# num_one.net
KiCad netlist of a schematic drawn in Altium Designer
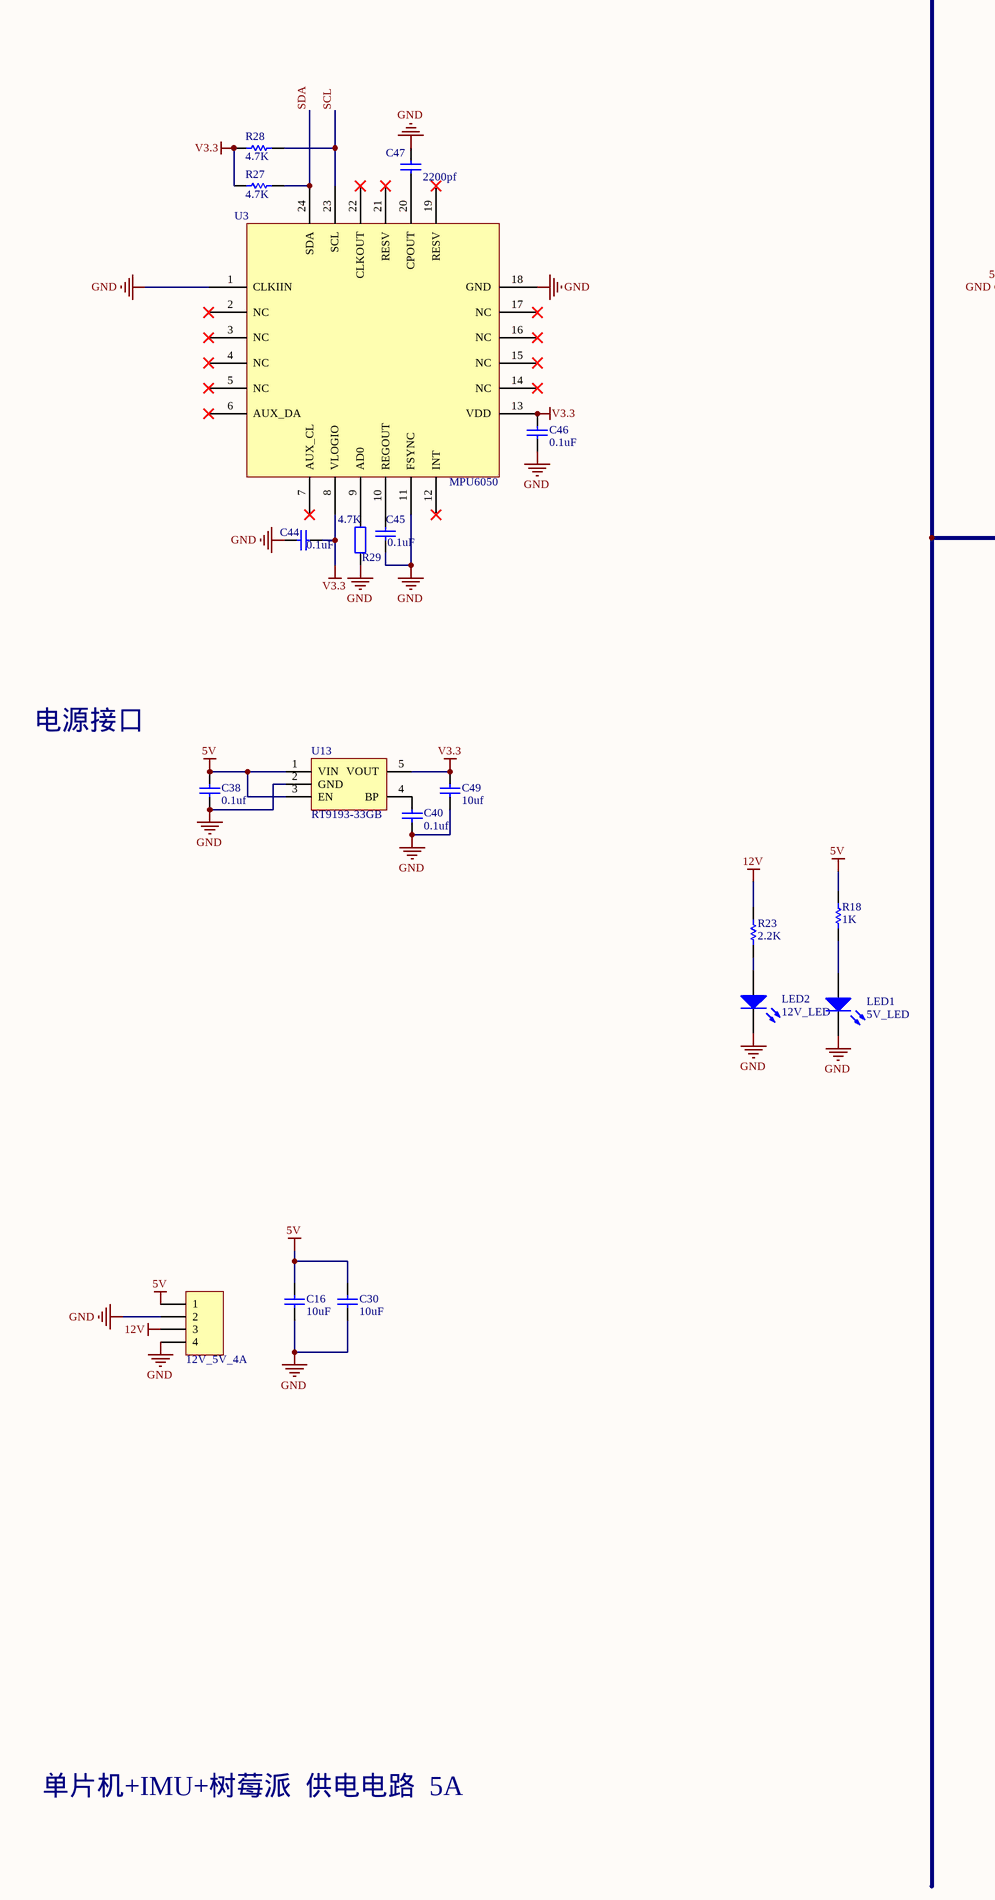
[diagram p0: num_one.SchDoc, left]
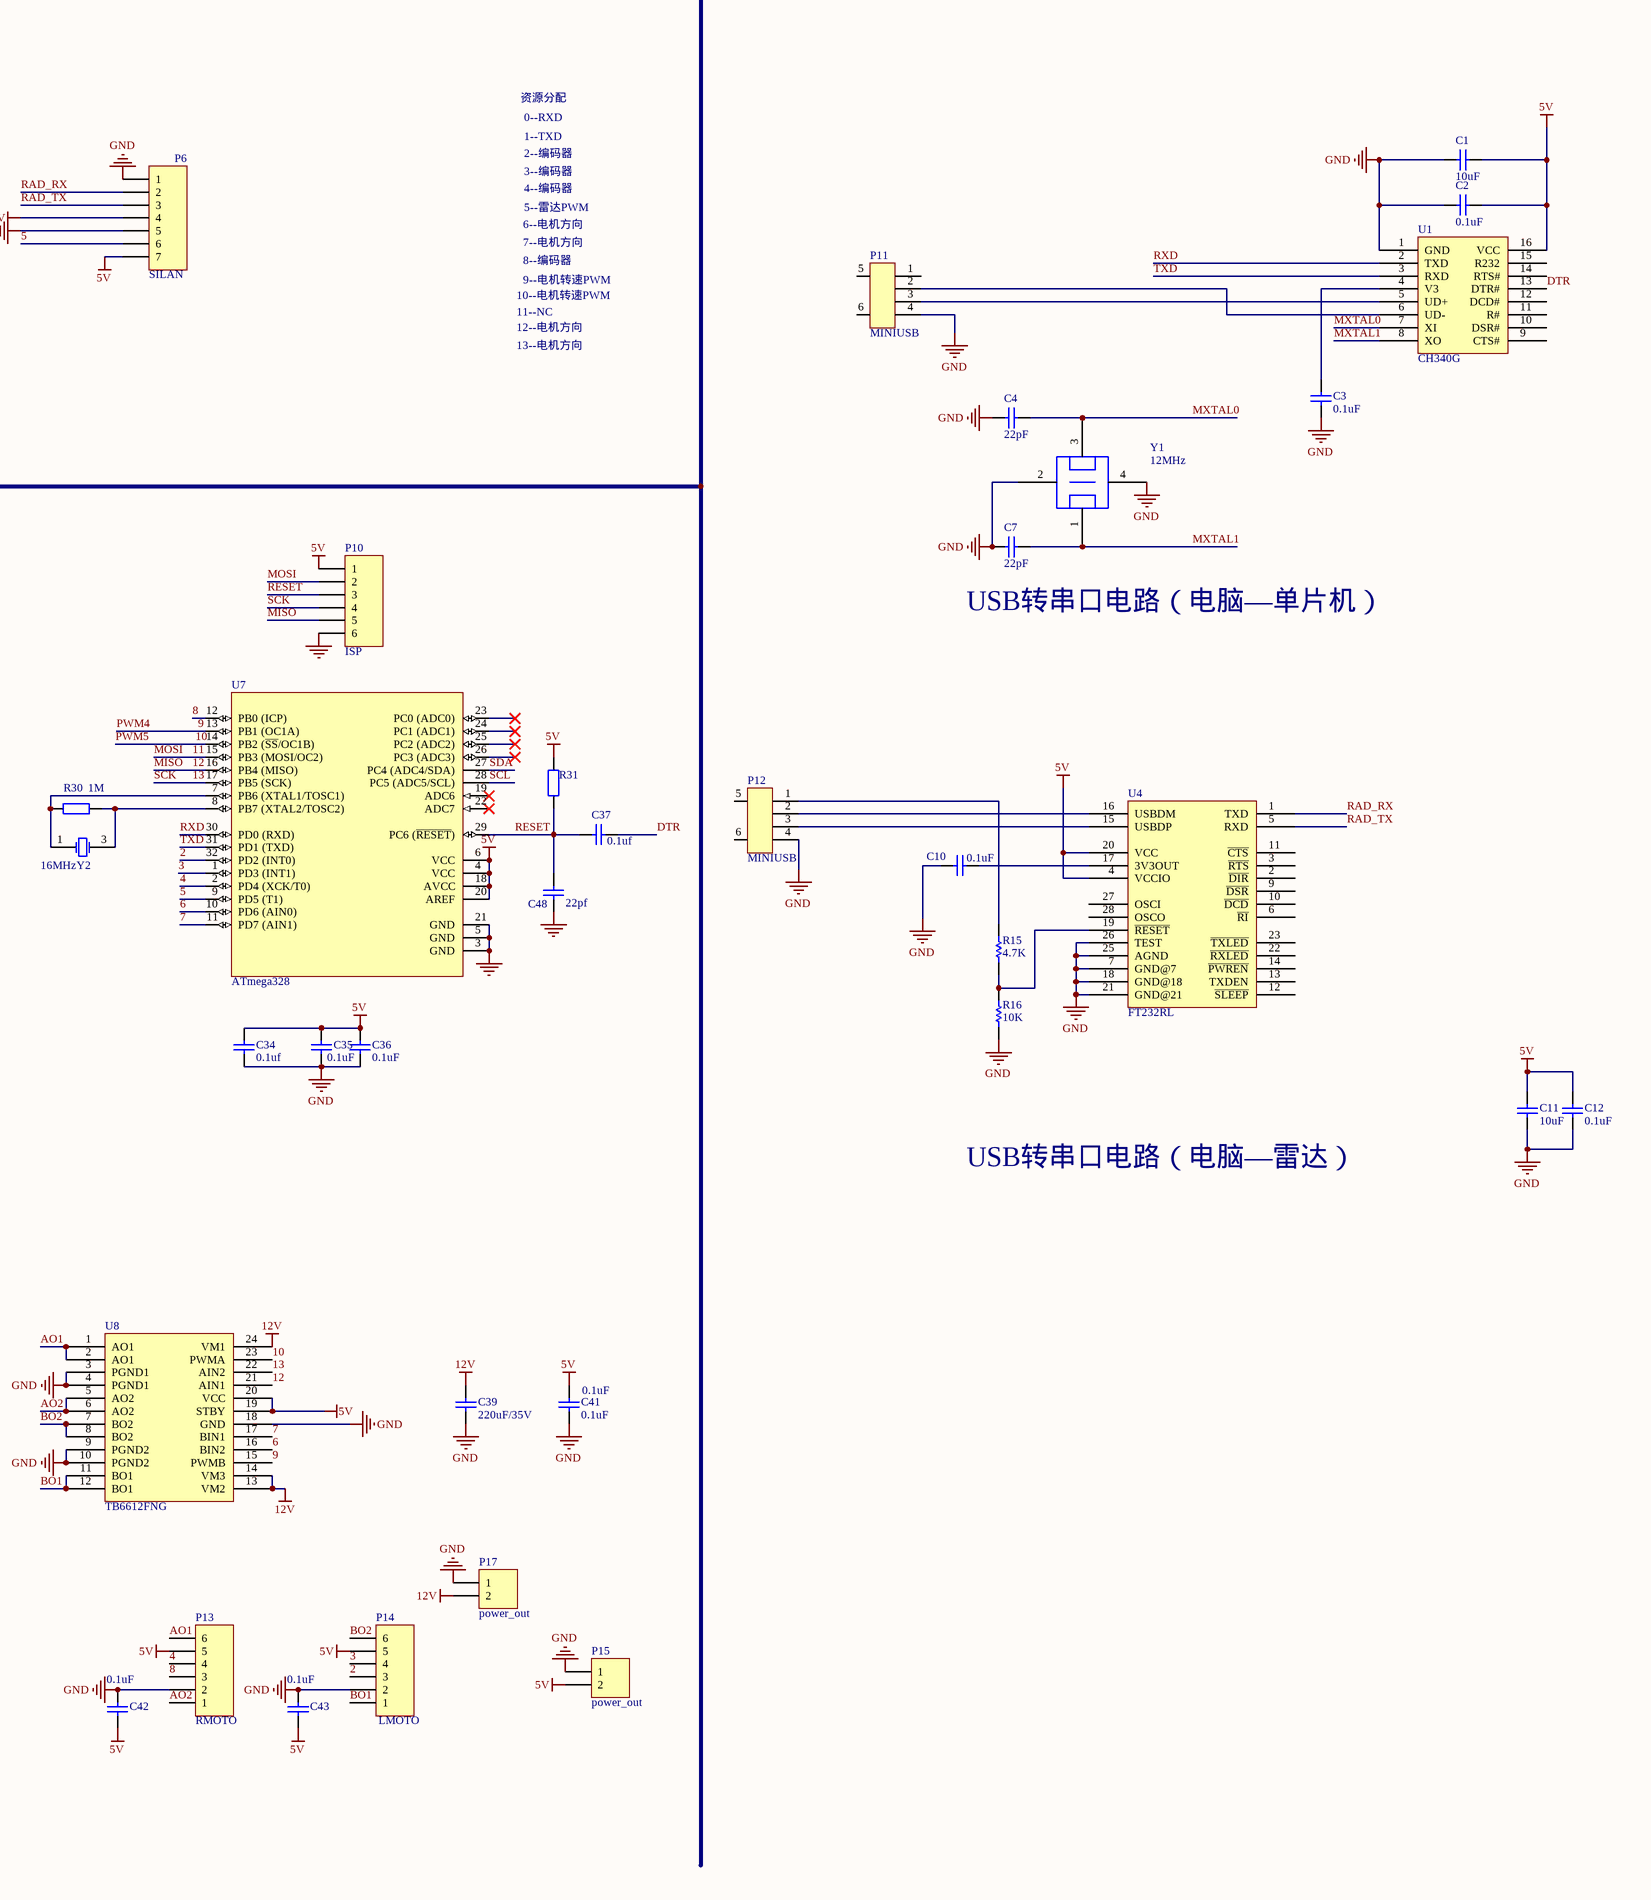
[diagram p1: num_one.SchDoc, right]

(export (version "E")
  (design (tool "Eeschema 10.0.6"))
  (components
    (comp (ref "C1") (value "10uF") (footprint "0805C") (libsource (lib "XS") (part "CAP")))
    (comp (ref "C2") (value "0.1uF") (footprint "0805C") (libsource (lib "XS") (part "CAP")))
    (comp (ref "C3") (value "0.1uF") (footprint "0805C") (libsource (lib "XS") (part "CAP")))
    (comp (ref "C4") (value "22pF") (footprint "0805C") (libsource (lib "XS") (part "CAP")))
    (comp (ref "C7") (value "22pF") (footprint "0805C") (libsource (lib "XS") (part "CAP")))
    (comp (ref "C10") (value "0.1uF") (footprint "0805C") (libsource (lib "XS") (part "CAP")))
    (comp (ref "C11") (value "10uF") (footprint "0805C") (libsource (lib "XS") (part "CAP")))
    (comp (ref "C12") (value "0.1uF") (footprint "0805C") (libsource (lib "XS") (part "CAP")))
    (comp (ref "C16") (value "10uF") (footprint "0805C") (libsource (lib "XS") (part "CAP")))
    (comp (ref "C30") (value "10uF") (footprint "0805C") (libsource (lib "XS") (part "CAP")))
    (comp (ref "C34")
      (value "0.1uf")
      (footprint "0805")
      (fields (field (name "PUBLISHER") "Altium Limited"))
      (libsource (lib "Miscellaneous Devices") (part "Cap"))
    )
    (comp (ref "C35")
      (value "0.1uF")
      (footprint "0805")
      (fields (field (name "PUBLISHER") "Altium Limited"))
      (libsource (lib "Miscellaneous Devices") (part "Cap"))
    )
    (comp (ref "C36")
      (value "0.1uF")
      (footprint "0805")
      (fields (field (name "PUBLISHER") "Altium Limited"))
      (libsource (lib "Miscellaneous Devices") (part "Cap"))
    )
    (comp (ref "C37")
      (value "0.1uf")
      (footprint "0805")
      (fields (field (name "PUBLISHER") "Altium Limited"))
      (libsource (lib "Miscellaneous Devices") (part "Cap"))
    )
    (comp (ref "C38")
      (value "0.1uf")
      (footprint "0805C")
      (description "capacitor")
      (fields (field (name "PUBLISHER") "Altium Limited"))
      (libsource (lib "Miscellaneous Devices") (part "Cap"))
    )
    (comp (ref "C39")
      (value "220uF/35V")
      (footprint "1210")
      (description "钽电容")
      (fields (field (name "PUBLISHER") "Altium Limited"))
      (libsource (lib "Miscellaneous Devices") (part "Cap"))
    )
    (comp (ref "C40")
      (value "0.1uf")
      (footprint "0805C")
      (description "Capacitor")
      (fields (field (name "PUBLISHER") "Altium Limited"))
      (libsource (lib "Miscellaneous Devices") (part "Cap"))
    )
    (comp (ref "C41")
      (value "0.1uF")
      (footprint "0805")
      (fields (field (name "ALTIUM_VALUE") "0.1uF") (field (name "PUBLISHER") "Altium Limited"))
      (libsource (lib "Miscellaneous Devices") (part "Cap"))
    )
    (comp (ref "C42")
      (value "0.1uF")
      (footprint "0805")
      (fields (field (name "PUBLISHER") "Altium Limited"))
      (libsource (lib "Miscellaneous Devices") (part "Cap"))
    )
    (comp (ref "C43")
      (value "0.1uF")
      (footprint "0805")
      (fields (field (name "PUBLISHER") "Altium Limited"))
      (libsource (lib "Miscellaneous Devices") (part "Cap"))
    )
    (comp (ref "C44")
      (value "0.1uF")
      (footprint "0805")
      (description "0805贴片电容")
      (fields (field (name "PUBLISHER") "Altium Limited"))
      (libsource (lib "Miscellaneous Devices") (part "Cap"))
    )
    (comp (ref "C45")
      (value "0.1uF")
      (footprint "0805")
      (description "0805贴片电容")
      (fields (field (name "PUBLISHER") "Altium Limited"))
      (libsource (lib "Miscellaneous Devices") (part "Cap"))
    )
    (comp (ref "C46")
      (value "0.1uF")
      (footprint "0805")
      (description "0805贴片电容")
      (fields (field (name "PUBLISHER") "Altium Limited"))
      (libsource (lib "Miscellaneous Devices") (part "Cap"))
    )
    (comp (ref "C47")
      (value "2200pf")
      (footprint "0805")
      (description "0805贴片电容")
      (fields (field (name "PUBLISHER") "Altium Limited"))
      (libsource (lib "Miscellaneous Devices") (part "Cap"))
    )
    (comp (ref "C48")
      (value "22pf")
      (footprint "0805")
      (fields (field (name "PUBLISHER") "Altium Limited"))
      (libsource (lib "Miscellaneous Devices") (part "Cap"))
    )
    (comp (ref "C49")
      (value "10uf")
      (footprint "0805C")
      (description "Capacitor")
      (fields (field (name "PUBLISHER") "Altium Limited"))
      (libsource (lib "Miscellaneous Devices") (part "Cap"))
    )
    (comp (ref "LED1") (value "5V_LED") (footprint "0805D") (libsource (lib "XS") (part "LED")))
    (comp (ref "LED2") (value "12V_LED") (footprint "0805D") (libsource (lib "XS") (part "LED")))
    (comp (ref "P2")
      (value "12V_5V_4A")
      (footprint "2.54-4P")
      (description "Header, 4-Pin")
      (fields (field (name "PUBLISHER") "Altium Limited"))
      (libsource (lib "Miscellaneous Connectors") (part "Header 4"))
    )
    (comp (ref "P6")
      (value "SILAN")
      (footprint "2.54-7P li")
      (description "Header, 7-Pin")
      (fields (field (name "PUBLISHER") "Altium Limited"))
      (libsource (lib "Miscellaneous Connectors") (part "Header 7"))
    )
    (comp (ref "P10")
      (value "ISP")
      (footprint "HDR1X6")
      (description "2.54-6P排针")
      (fields (field (name "PUBLISHER") "Altium Limited"))
      (libsource (lib "") (part "Header 6_1"))
    )
    (comp (ref "P11")
      (value "MINIUSB")
      (footprint "USB_MINI")
      (description "贴片")
      (libsource (lib "XS") (part "USB-B"))
    )
    (comp (ref "P12")
      (value "MINIUSB")
      (footprint "USB_MINI")
      (description "贴片")
      (libsource (lib "XS") (part "USB-B"))
    )
    (comp (ref "P13")
      (value "RMOTO")
      (footprint "2.54-6P")
      (description "2.54-6P卧贴")
      (fields (field (name "PUBLISHER") "Altium Limited"))
      (libsource (lib "Miscellaneous Connectors") (part "Header 6"))
    )
    (comp (ref "P14")
      (value "LMOTO")
      (footprint "2.54-6P")
      (description "2.54-6P卧贴")
      (fields (field (name "PUBLISHER") "Altium Limited"))
      (libsource (lib "Miscellaneous Connectors") (part "Header 6"))
    )
    (comp (ref "P15")
      (value "power_out")
      (footprint "2.54-2P")
      (description "2.54-2P卧贴")
      (libsource (lib "XS") (part "2P"))
    )
    (comp (ref "P17")
      (value "power_out")
      (footprint "2.54-2P")
      (description "2.54-2P卧贴")
      (libsource (lib "XS") (part "2P"))
    )
    (comp (ref "R15") (value "4.7K") (footprint "0805_RES") (libsource (lib "XS") (part "RES")))
    (comp (ref "R16") (value "10K") (footprint "0805_RES") (libsource (lib "XS") (part "RES")))
    (comp (ref "R18") (value "1K") (footprint "0805_RES") (libsource (lib "XS") (part "RES")))
    (comp (ref "R23") (value "2.2K") (footprint "0805_RES") (libsource (lib "XS") (part "RES")))
    (comp (ref "R27") (value "4.7K") (footprint "0805") (libsource (lib "XS") (part "RES")))
    (comp (ref "R28") (value "4.7K") (footprint "0805") (libsource (lib "XS") (part "RES")))
    (comp (ref "R29")
      (value "4.7K")
      (footprint "0805")
      (description "Resistor")
      (fields (field (name "PUBLISHER") "Altium Limited"))
      (libsource (lib "") (part "Res2_1"))
    )
    (comp (ref "R30")
      (value "1M")
      (footprint "0805")
      (fields (field (name "PUBLISHER") "Altium Limited"))
      (libsource (lib "Miscellaneous Devices") (part "Res2"))
    )
    (comp (ref "R31")
      (value "100K")
      (footprint "0805")
      (fields (field (name "PUBLISHER") "Altium Limited"))
      (libsource (lib "") (part "Res2_2"))
    )
    (comp (ref "U1")
      (value "CH340G")
      (footprint "SO-16_CH340")
      (description "USB芯片")
      (libsource (lib "XS") (part "CH340G"))
    )
    (comp (ref "U3") (value "MPU6050") (footprint "QFN24") (libsource (lib "NEW") (part "MPU6050")))
    (comp (ref "U4")
      (value "FT232RL")
      (footprint "FT232RL")
      (description "USB芯片")
      (libsource (lib "XS") (part "FT232RL"))
    )
    (comp (ref "U7")
      (value "ATmega328")
      (footprint "QFP32")
      (description "8位单片机")
      (fields (field (name "PUBLISHER") "Altium Limited"))
      (libsource (lib "Atmel Microcontroller 8-Bit AVR") (part "ATmega8-16AC"))
    )
    (comp (ref "U8")
      (value "TB6612FNG")
      (footprint "SSOP24")
      (description "电机驱动芯片")
      (libsource (lib "NEW") (part "TB6612"))
    )
    (comp (ref "U13")
      (value "RT9193-33GB")
      (footprint "SOT23-5")
      (description "电源芯片")
      (libsource (lib "YS_BDC_V1") (part "RT9193"))
    )
    (comp (ref "Y1")
      (value "12MHz")
      (footprint "XTAL-3225")
      (description "有源晶振")
      (libsource (lib "XS") (part "XTAL"))
    )
    (comp (ref "Y2")
      (value "16MHz")
      (footprint "TCJZ-3")
      (description "3212村田陶瓷晶振")
      (fields (field (name "PUBLISHER") "Altium Limited"))
      (libsource (lib "Miscellaneous Devices") (part "XTAL"))
    )
  )
  (nets
    (net (code "1") (name "/2") (class "Default")
      (node (ref "P14") (pin "3") (pinfunction "3_3") (pintype "passive"))
      (node (ref "U7") (pin "32") (pinfunction "PD2_(INT0)_32") (pintype "bidirectional"))
    )
    (net (code "2") (name "/3") (class "Default")
      (node (ref "P14") (pin "4") (pinfunction "4_4") (pintype "passive"))
      (node (ref "U7") (pin "1") (pinfunction "PD3_(INT1)_1") (pintype "bidirectional"))
    )
    (net (code "3") (name "/4") (class "Default")
      (node (ref "P13") (pin "4") (pinfunction "4_4") (pintype "passive"))
      (node (ref "U7") (pin "2") (pinfunction "PD4_(XCK/T0)_2") (pintype "bidirectional"))
    )
    (net (code "4") (name "/5") (class "Default")
      (node (ref "P6") (pin "6") (pinfunction "6_6") (pintype "passive"))
      (node (ref "U7") (pin "9") (pinfunction "PD5_(T1)_9") (pintype "bidirectional"))
    )
    (net (code "5") (name "/6") (class "Default")
      (node (ref "U7") (pin "10") (pinfunction "PD6_(AIN0)_10") (pintype "bidirectional"))
      (node (ref "U8") (pin "16") (pinfunction "BIN2_16") (pintype "passive"))
    )
    (net (code "6") (name "/7") (class "Default")
      (node (ref "U7") (pin "11") (pinfunction "PD7_(AIN1)_11") (pintype "bidirectional"))
      (node (ref "U8") (pin "17") (pinfunction "BIN1_17") (pintype "passive"))
    )
    (net (code "7") (name "/8") (class "Default")
      (node (ref "P13") (pin "3") (pinfunction "3_3") (pintype "passive"))
      (node (ref "U7") (pin "12") (pinfunction "PB0_(ICP)_12") (pintype "bidirectional"))
    )
    (net (code "8") (name "/9") (class "Default")
      (node (ref "U7") (pin "13") (pinfunction "PB1_(OC1A)_13") (pintype "bidirectional"))
      (node (ref "U8") (pin "15") (pinfunction "PWMB_15") (pintype "passive"))
    )
    (net (code "9") (name "/10") (class "Default")
      (node (ref "U7") (pin "14") (pinfunction "PB2_(~{SS}/OC1B)_14") (pintype "bidirectional"))
      (node (ref "U8") (pin "23") (pinfunction "PWMA_23") (pintype "passive"))
    )
    (net (code "10") (name "/11") (class "Default")
      (node (ref "P10") (pin "2") (pinfunction "2_2") (pintype "passive"))
      (node (ref "U7") (pin "15") (pinfunction "PB3_(MOSI/OC2)_15") (pintype "bidirectional"))
    )
    (net (code "11") (name "/12") (class "Default")
      (node (ref "P10") (pin "5") (pinfunction "5_5") (pintype "passive"))
      (node (ref "U7") (pin "16") (pinfunction "PB4_(MISO)_16") (pintype "bidirectional"))
      (node (ref "U8") (pin "21") (pinfunction "AIN1_21") (pintype "passive"))
    )
    (net (code "12") (name "/13") (class "Default")
      (node (ref "P10") (pin "4") (pinfunction "4_4") (pintype "passive"))
      (node (ref "U7") (pin "17") (pinfunction "PB5_(SCK)_17") (pintype "bidirectional"))
      (node (ref "U8") (pin "22") (pinfunction "AIN2_22") (pintype "passive"))
    )
    (net (code "13") (name "/AO1") (class "Default")
      (node (ref "P13") (pin "6") (pinfunction "6_6") (pintype "passive"))
      (node (ref "U8") (pin "1") (pinfunction "AO1_1") (pintype "passive"))
      (node (ref "U8") (pin "2") (pinfunction "AO1_2") (pintype "passive"))
    )
    (net (code "14") (name "/AO2") (class "Default")
      (node (ref "P13") (pin "1") (pinfunction "1_1") (pintype "passive"))
      (node (ref "U8") (pin "5") (pinfunction "AO2_5") (pintype "passive"))
      (node (ref "U8") (pin "6") (pinfunction "AO2_6") (pintype "passive"))
    )
    (net (code "15") (name "/BO1") (class "Default")
      (node (ref "P14") (pin "1") (pinfunction "1_1") (pintype "passive"))
      (node (ref "U8") (pin "11") (pinfunction "BO1_11") (pintype "passive"))
      (node (ref "U8") (pin "12") (pinfunction "BO1_12") (pintype "passive"))
    )
    (net (code "16") (name "/BO2") (class "Default")
      (node (ref "P14") (pin "6") (pinfunction "6_6") (pintype "passive"))
      (node (ref "U8") (pin "7") (pinfunction "BO2_7") (pintype "passive"))
      (node (ref "U8") (pin "8") (pinfunction "BO2_8") (pintype "passive"))
    )
    (net (code "17") (name "/DTR") (class "Default")
      (node (ref "C37") (pin "1") (pinfunction "1_1") (pintype "passive"))
      (node (ref "U1") (pin "13") (pinfunction "DTR#_13") (pintype "passive"))
    )
    (net (code "18") (name "/MXTAL0") (class "Default")
      (node (ref "C4") (pin "1") (pinfunction "1_1") (pintype "passive"))
      (node (ref "U1") (pin "7") (pinfunction "XI_7") (pintype "passive"))
      (node (ref "Y1") (pin "3") (pinfunction "3_3") (pintype "passive"))
    )
    (net (code "19") (name "/MXTAL1") (class "Default")
      (node (ref "C7") (pin "1") (pinfunction "1_1") (pintype "passive"))
      (node (ref "U1") (pin "8") (pinfunction "XO_8") (pintype "passive"))
      (node (ref "Y1") (pin "1") (pinfunction "1_1") (pintype "passive"))
    )
    (net (code "20") (name "/RAD_RX") (class "Default")
      (node (ref "P6") (pin "2") (pinfunction "2_2") (pintype "passive"))
      (node (ref "U4") (pin "1") (pinfunction "TXD_1") (pintype "passive"))
    )
    (net (code "21") (name "/RAD_TX") (class "Default")
      (node (ref "P6") (pin "3") (pinfunction "3_3") (pintype "passive"))
      (node (ref "U4") (pin "5") (pinfunction "RXD_5") (pintype "passive"))
    )
    (net (code "22") (name "/RESET") (class "Default")
      (node (ref "C37") (pin "2") (pinfunction "2_2") (pintype "passive"))
      (node (ref "C48") (pin "2") (pinfunction "2_2") (pintype "passive"))
      (node (ref "P10") (pin "3") (pinfunction "3_3") (pintype "passive"))
      (node (ref "R31") (pin "2") (pinfunction "2_2") (pintype "passive"))
      (node (ref "U7") (pin "29") (pinfunction "PC6_(~{RESET})_29") (pintype "bidirectional"))
    )
    (net (code "23") (name "/RXD") (class "Default")
      (node (ref "U1") (pin "2") (pinfunction "TXD_2") (pintype "passive"))
      (node (ref "U7") (pin "30") (pinfunction "PD0_(RXD)_30") (pintype "bidirectional"))
    )
    (net (code "24") (name "/SCL") (class "Default")
      (node (ref "R28") (pin "2") (pinfunction "2_2") (pintype "passive"))
      (node (ref "U3") (pin "23") (pinfunction "SCL_23") (pintype "passive"))
      (node (ref "U7") (pin "28") (pinfunction "PC5_(ADC5/SCL)_28") (pintype "passive"))
    )
    (net (code "25") (name "/SDA") (class "Default")
      (node (ref "R27") (pin "2") (pinfunction "2_2") (pintype "passive"))
      (node (ref "U3") (pin "24") (pinfunction "SDA_24") (pintype "passive"))
      (node (ref "U7") (pin "27") (pinfunction "PC4_(ADC4/SDA)_27") (pintype "passive"))
    )
    (net (code "26") (name "/TXD") (class "Default")
      (node (ref "U1") (pin "3") (pinfunction "RXD_3") (pintype "passive"))
      (node (ref "U7") (pin "31") (pinfunction "PD1_(TXD)_31") (pintype "bidirectional"))
    )
    (net (code "27") (name "5V") (class "Default")
      (node (ref "C1") (pin "1") (pinfunction "1_1") (pintype "passive"))
      (node (ref "C11") (pin "1") (pinfunction "1_1") (pintype "passive"))
      (node (ref "C12") (pin "1") (pinfunction "1_1") (pintype "passive"))
      (node (ref "C16") (pin "2") (pinfunction "2_2") (pintype "passive"))
      (node (ref "C2") (pin "1") (pinfunction "1_1") (pintype "passive"))
      (node (ref "C30") (pin "2") (pinfunction "2_2") (pintype "passive"))
      (node (ref "C34") (pin "2") (pinfunction "2_2") (pintype "passive"))
      (node (ref "C35") (pin "2") (pinfunction "2_2") (pintype "passive"))
      (node (ref "C36") (pin "2") (pinfunction "2_2") (pintype "passive"))
      (node (ref "C38") (pin "2") (pinfunction "2_2") (pintype "passive"))
      (node (ref "C41") (pin "2") (pinfunction "2_2") (pintype "passive"))
      (node (ref "C42") (pin "2") (pinfunction "2_2") (pintype "passive"))
      (node (ref "C43") (pin "2") (pinfunction "2_2") (pintype "passive"))
      (node (ref "P10") (pin "1") (pinfunction "1_1") (pintype "passive"))
      (node (ref "P13") (pin "5") (pinfunction "5_5") (pintype "passive"))
      (node (ref "P14") (pin "5") (pinfunction "5_5") (pintype "passive"))
      (node (ref "P15") (pin "2") (pinfunction "2_2") (pintype "passive"))
      (node (ref "P2") (pin "1") (pinfunction "1_1") (pintype "passive"))
      (node (ref "P6") (pin "4") (pinfunction "4_4") (pintype "passive"))
      (node (ref "P6") (pin "7") (pinfunction "7_7") (pintype "passive"))
      (node (ref "R18") (pin "1") (pinfunction "1_1") (pintype "passive"))
      (node (ref "R31") (pin "1") (pinfunction "1_1") (pintype "passive"))
      (node (ref "U1") (pin "16") (pinfunction "VCC_16") (pintype "passive"))
      (node (ref "U13") (pin "1") (pinfunction "VIN_1") (pintype "passive"))
      (node (ref "U13") (pin "3") (pinfunction "EN_3") (pintype "passive"))
      (node (ref "U4") (pin "20") (pinfunction "VCC_20") (pintype "passive"))
      (node (ref "U4") (pin "4") (pinfunction "VCCIO_4") (pintype "passive"))
      (node (ref "U7") (pin "18") (pinfunction "AVCC_18") (pintype "power_in"))
      (node (ref "U7") (pin "20") (pinfunction "AREF_20") (pintype "passive"))
      (node (ref "U7") (pin "4") (pinfunction "VCC_4") (pintype "power_in"))
      (node (ref "U7") (pin "6") (pinfunction "VCC_6") (pintype "power_in"))
      (node (ref "U8") (pin "19") (pinfunction "STBY_19") (pintype "passive"))
      (node (ref "U8") (pin "20") (pinfunction "VCC_20") (pintype "passive"))
    )
    (net (code "28") (name "12V") (class "Default")
      (node (ref "C39") (pin "2") (pinfunction "2_2") (pintype "passive"))
      (node (ref "P17") (pin "2") (pinfunction "2_2") (pintype "passive"))
      (node (ref "P2") (pin "3") (pinfunction "3_3") (pintype "passive"))
      (node (ref "R23") (pin "1") (pinfunction "1_1") (pintype "passive"))
      (node (ref "U8") (pin "13") (pinfunction "VM2_13") (pintype "passive"))
      (node (ref "U8") (pin "14") (pinfunction "VM3_14") (pintype "passive"))
      (node (ref "U8") (pin "24") (pinfunction "VM1_24") (pintype "passive"))
    )
    (net (code "29") (name "GND") (class "Default")
      (node (ref "C1") (pin "2") (pinfunction "2_2") (pintype "passive"))
      (node (ref "C10") (pin "2") (pinfunction "2_2") (pintype "passive"))
      (node (ref "C11") (pin "2") (pinfunction "2_2") (pintype "passive"))
      (node (ref "C12") (pin "2") (pinfunction "2_2") (pintype "passive"))
      (node (ref "C16") (pin "1") (pinfunction "1_1") (pintype "passive"))
      (node (ref "C2") (pin "2") (pinfunction "2_2") (pintype "passive"))
      (node (ref "C3") (pin "1") (pinfunction "1_1") (pintype "passive"))
      (node (ref "C30") (pin "1") (pinfunction "1_1") (pintype "passive"))
      (node (ref "C34") (pin "1") (pinfunction "1_1") (pintype "passive"))
      (node (ref "C35") (pin "1") (pinfunction "1_1") (pintype "passive"))
      (node (ref "C36") (pin "1") (pinfunction "1_1") (pintype "passive"))
      (node (ref "C38") (pin "1") (pinfunction "1_1") (pintype "passive"))
      (node (ref "C39") (pin "1") (pinfunction "1_1") (pintype "passive"))
      (node (ref "C4") (pin "2") (pinfunction "2_2") (pintype "passive"))
      (node (ref "C40") (pin "1") (pinfunction "1_1") (pintype "passive"))
      (node (ref "C41") (pin "1") (pinfunction "1_1") (pintype "passive"))
      (node (ref "C42") (pin "1") (pinfunction "1_1") (pintype "passive"))
      (node (ref "C43") (pin "1") (pinfunction "1_1") (pintype "passive"))
      (node (ref "C44") (pin "2") (pinfunction "2_2") (pintype "passive"))
      (node (ref "C45") (pin "1") (pinfunction "1_1") (pintype "passive"))
      (node (ref "C46") (pin "1") (pinfunction "1_1") (pintype "passive"))
      (node (ref "C47") (pin "2") (pinfunction "2_2") (pintype "passive"))
      (node (ref "C48") (pin "1") (pinfunction "1_1") (pintype "passive"))
      (node (ref "C49") (pin "1") (pinfunction "1_1") (pintype "passive"))
      (node (ref "C7") (pin "2") (pinfunction "2_2") (pintype "passive"))
      (node (ref "LED1") (pin "K") (pinfunction "K_K") (pintype "passive"))
      (node (ref "LED2") (pin "K") (pinfunction "K_K") (pintype "passive"))
      (node (ref "P10") (pin "6") (pinfunction "6_6") (pintype "passive"))
      (node (ref "P11") (pin "4") (pinfunction "4_4") (pintype "passive"))
      (node (ref "P12") (pin "4") (pinfunction "4_4") (pintype "passive"))
      (node (ref "P13") (pin "2") (pinfunction "2_2") (pintype "passive"))
      (node (ref "P14") (pin "2") (pinfunction "2_2") (pintype "passive"))
      (node (ref "P15") (pin "1") (pinfunction "1_1") (pintype "passive"))
      (node (ref "P17") (pin "1") (pinfunction "1_1") (pintype "passive"))
      (node (ref "P2") (pin "2") (pinfunction "2_2") (pintype "passive"))
      (node (ref "P2") (pin "4") (pinfunction "4_4") (pintype "passive"))
      (node (ref "P6") (pin "1") (pinfunction "1_1") (pintype "passive"))
      (node (ref "P6") (pin "5") (pinfunction "5_5") (pintype "passive"))
      (node (ref "R16") (pin "2") (pinfunction "2_2") (pintype "passive"))
      (node (ref "R29") (pin "1") (pinfunction "1_1") (pintype "passive"))
      (node (ref "U1") (pin "1") (pinfunction "GND_1") (pintype "passive"))
      (node (ref "U13") (pin "2") (pinfunction "GND_2") (pintype "passive"))
      (node (ref "U3") (pin "1") (pinfunction "CLKIIN_1") (pintype "passive"))
      (node (ref "U3") (pin "11") (pinfunction "FSYNC_11") (pintype "passive"))
      (node (ref "U3") (pin "18") (pinfunction "GND_18") (pintype "passive"))
      (node (ref "U4") (pin "18") (pinfunction "GND@18_18") (pintype "passive"))
      (node (ref "U4") (pin "21") (pinfunction "GND@21_21") (pintype "passive"))
      (node (ref "U4") (pin "25") (pinfunction "AGND_25") (pintype "passive"))
      (node (ref "U4") (pin "26") (pinfunction "TEST_26") (pintype "passive"))
      (node (ref "U4") (pin "7") (pinfunction "GND@7_7") (pintype "passive"))
      (node (ref "U7") (pin "21") (pinfunction "GND_21") (pintype "power_in"))
      (node (ref "U7") (pin "3") (pinfunction "GND_3") (pintype "power_in"))
      (node (ref "U7") (pin "5") (pinfunction "GND_5") (pintype "power_in"))
      (node (ref "U8") (pin "10") (pinfunction "PGND2_10") (pintype "passive"))
      (node (ref "U8") (pin "18") (pinfunction "GND_18") (pintype "passive"))
      (node (ref "U8") (pin "3") (pinfunction "PGND1_3") (pintype "passive"))
      (node (ref "U8") (pin "4") (pinfunction "PGND1_4") (pintype "passive"))
      (node (ref "U8") (pin "9") (pinfunction "PGND2_9") (pintype "passive"))
      (node (ref "Y1") (pin "2") (pinfunction "2_2") (pintype "passive"))
      (node (ref "Y1") (pin "4") (pinfunction "4_4") (pintype "passive"))
    )
    (net (code "30") (name "Net-(LED1-PadA)") (class "Default")
      (node (ref "LED1") (pin "A") (pinfunction "A_A") (pintype "passive"))
      (node (ref "R18") (pin "2") (pinfunction "2_2") (pintype "passive"))
    )
    (net (code "31") (name "Net-(LED2-PadA)") (class "Default")
      (node (ref "LED2") (pin "A") (pinfunction "A_A") (pintype "passive"))
      (node (ref "R23") (pin "2") (pinfunction "2_2") (pintype "passive"))
    )
    (net (code "32") (name "Net-(P12-Pad1)") (class "Default")
      (node (ref "P12") (pin "1") (pinfunction "1_1") (pintype "passive"))
      (node (ref "R15") (pin "1") (pinfunction "1_1") (pintype "passive"))
    )
    (net (code "33") (name "Net-(U1-UD+)") (class "Default")
      (node (ref "P11") (pin "3") (pinfunction "3_3") (pintype "passive"))
      (node (ref "U1") (pin "5") (pinfunction "UD+_5") (pintype "passive"))
    )
    (net (code "34") (name "Net-(U1-UD-)") (class "Default")
      (node (ref "P11") (pin "2") (pinfunction "2_2") (pintype "passive"))
      (node (ref "U1") (pin "6") (pinfunction "UD-_6") (pintype "passive"))
    )
    (net (code "35") (name "Net-(U1-V3)") (class "Default")
      (node (ref "C3") (pin "2") (pinfunction "2_2") (pintype "passive"))
      (node (ref "U1") (pin "4") (pinfunction "V3_4") (pintype "passive"))
    )
    (net (code "36") (name "Net-(U3-AD0)") (class "Default")
      (node (ref "R29") (pin "2") (pinfunction "2_2") (pintype "passive"))
      (node (ref "U3") (pin "9") (pinfunction "AD0_9") (pintype "passive"))
    )
    (net (code "37") (name "Net-(U3-CPOUT)") (class "Default")
      (node (ref "C47") (pin "1") (pinfunction "1_1") (pintype "passive"))
      (node (ref "U3") (pin "20") (pinfunction "CPOUT_20") (pintype "passive"))
    )
    (net (code "38") (name "Net-(U3-REGOUT)") (class "Default")
      (node (ref "C45") (pin "2") (pinfunction "2_2") (pintype "passive"))
      (node (ref "U3") (pin "10") (pinfunction "REGOUT_10") (pintype "passive"))
    )
    (net (code "39") (name "Net-(U4-3V3OUT)") (class "Default")
      (node (ref "C10") (pin "1") (pinfunction "1_1") (pintype "passive"))
      (node (ref "U4") (pin "17") (pinfunction "3V3OUT_17") (pintype "passive"))
    )
    (net (code "40") (name "Net-(U4-USBDM)") (class "Default")
      (node (ref "P12") (pin "2") (pinfunction "2_2") (pintype "passive"))
      (node (ref "U4") (pin "16") (pinfunction "USBDM_16") (pintype "passive"))
    )
    (net (code "41") (name "Net-(U4-USBDP)") (class "Default")
      (node (ref "P12") (pin "3") (pinfunction "3_3") (pintype "passive"))
      (node (ref "U4") (pin "15") (pinfunction "USBDP_15") (pintype "passive"))
    )
    (net (code "42") (name "Net-(U4-~{RESET})") (class "Default")
      (node (ref "R15") (pin "2") (pinfunction "2_2") (pintype "passive"))
      (node (ref "R16") (pin "1") (pinfunction "1_1") (pintype "passive"))
      (node (ref "U4") (pin "19") (pinfunction "~{RESET}_19") (pintype "passive"))
    )
    (net (code "43") (name "Net-(U7-PB6_(XTAL1{slash}TOSC1))") (class "Default")
      (node (ref "R30") (pin "1") (pinfunction "1_1") (pintype "passive"))
      (node (ref "U7") (pin "7") (pinfunction "PB6_(XTAL1/TOSC1)_7") (pintype "bidirectional"))
      (node (ref "Y2") (pin "1") (pinfunction "OSC1_1") (pintype "passive"))
    )
    (net (code "44") (name "Net-(U7-PB7_(XTAL2{slash}TOSC2))") (class "Default")
      (node (ref "R30") (pin "2") (pinfunction "2_2") (pintype "passive"))
      (node (ref "U7") (pin "8") (pinfunction "PB7_(XTAL2/TOSC2)_8") (pintype "bidirectional"))
      (node (ref "Y2") (pin "3") (pinfunction "OSC2_3") (pintype "passive"))
    )
    (net (code "45") (name "Net-(U13-BP)") (class "Default")
      (node (ref "C40") (pin "2") (pinfunction "2_2") (pintype "passive"))
      (node (ref "U13") (pin "4") (pinfunction "BP_4") (pintype "passive"))
    )
    (net (code "46") (name "V3.3") (class "Default")
      (node (ref "C44") (pin "1") (pinfunction "1_1") (pintype "passive"))
      (node (ref "C46") (pin "2") (pinfunction "2_2") (pintype "passive"))
      (node (ref "C49") (pin "2") (pinfunction "2_2") (pintype "passive"))
      (node (ref "R27") (pin "1") (pinfunction "1_1") (pintype "passive"))
      (node (ref "R28") (pin "1") (pinfunction "1_1") (pintype "passive"))
      (node (ref "U13") (pin "5") (pinfunction "VOUT_5") (pintype "passive"))
      (node (ref "U3") (pin "13") (pinfunction "VDD_13") (pintype "passive"))
      (node (ref "U3") (pin "8") (pinfunction "VLOGIO_8") (pintype "passive"))
    )
    (net (code "47") (name "unconnected-(P11-Pad1)") (class "Default")
      (node (ref "P11") (pin "1") (pinfunction "1_1") (pintype "passive"))
    )
    (net (code "48") (name "unconnected-(P11-Pad5)") (class "Default")
      (node (ref "P11") (pin "5") (pinfunction "5_5") (pintype "passive"))
    )
    (net (code "49") (name "unconnected-(P11-Pad6)") (class "Default")
      (node (ref "P11") (pin "6") (pinfunction "6_6") (pintype "passive"))
    )
    (net (code "50") (name "unconnected-(P12-Pad5)") (class "Default")
      (node (ref "P12") (pin "5") (pinfunction "5_5") (pintype "passive"))
    )
    (net (code "51") (name "unconnected-(P12-Pad6)") (class "Default")
      (node (ref "P12") (pin "6") (pinfunction "6_6") (pintype "passive"))
    )
    (net (code "52") (name "unconnected-(U1-CTS#-Pad9)") (class "Default")
      (node (ref "U1") (pin "9") (pinfunction "CTS#_9") (pintype "passive"))
    )
    (net (code "53") (name "unconnected-(U1-DCD#-Pad12)") (class "Default")
      (node (ref "U1") (pin "12") (pinfunction "DCD#_12") (pintype "passive"))
    )
    (net (code "54") (name "unconnected-(U1-DSR#-Pad10)") (class "Default")
      (node (ref "U1") (pin "10") (pinfunction "DSR#_10") (pintype "passive"))
    )
    (net (code "55") (name "unconnected-(U1-R#-Pad11)") (class "Default")
      (node (ref "U1") (pin "11") (pinfunction "R#_11") (pintype "passive"))
    )
    (net (code "56") (name "unconnected-(U1-R232-Pad15)") (class "Default")
      (node (ref "U1") (pin "15") (pinfunction "R232_15") (pintype "passive"))
    )
    (net (code "57") (name "unconnected-(U1-RTS#-Pad14)") (class "Default")
      (node (ref "U1") (pin "14") (pinfunction "RTS#_14") (pintype "passive"))
    )
    (net (code "58") (name "unconnected-(U3-AUX_CL-Pad7)") (class "Default")
      (node (ref "U3") (pin "7") (pinfunction "AUX_CL_7") (pintype "passive+no_connect"))
    )
    (net (code "59") (name "unconnected-(U3-AUX_DA-Pad6)") (class "Default")
      (node (ref "U3") (pin "6") (pinfunction "AUX_DA_6") (pintype "passive+no_connect"))
    )
    (net (code "60") (name "unconnected-(U3-CLKOUT-Pad22)") (class "Default")
      (node (ref "U3") (pin "22") (pinfunction "CLKOUT_22") (pintype "passive+no_connect"))
    )
    (net (code "61") (name "unconnected-(U3-INT-Pad12)") (class "Default")
      (node (ref "U3") (pin "12") (pinfunction "INT_12") (pintype "passive+no_connect"))
    )
    (net (code "62") (name "unconnected-(U3-NC-Pad2)") (class "Default")
      (node (ref "U3") (pin "2") (pinfunction "NC_2") (pintype "passive+no_connect"))
    )
    (net (code "63") (name "unconnected-(U3-NC-Pad3)") (class "Default")
      (node (ref "U3") (pin "3") (pinfunction "NC_3") (pintype "passive+no_connect"))
    )
    (net (code "64") (name "unconnected-(U3-NC-Pad4)") (class "Default")
      (node (ref "U3") (pin "4") (pinfunction "NC_4") (pintype "passive+no_connect"))
    )
    (net (code "65") (name "unconnected-(U3-NC-Pad5)") (class "Default")
      (node (ref "U3") (pin "5") (pinfunction "NC_5") (pintype "passive+no_connect"))
    )
    (net (code "66") (name "unconnected-(U3-NC-Pad14)") (class "Default")
      (node (ref "U3") (pin "14") (pinfunction "NC_14") (pintype "passive+no_connect"))
    )
    (net (code "67") (name "unconnected-(U3-NC-Pad15)") (class "Default")
      (node (ref "U3") (pin "15") (pinfunction "NC_15") (pintype "passive+no_connect"))
    )
    (net (code "68") (name "unconnected-(U3-NC-Pad16)") (class "Default")
      (node (ref "U3") (pin "16") (pinfunction "NC_16") (pintype "passive+no_connect"))
    )
    (net (code "69") (name "unconnected-(U3-NC-Pad17)") (class "Default")
      (node (ref "U3") (pin "17") (pinfunction "NC_17") (pintype "passive+no_connect"))
    )
    (net (code "70") (name "unconnected-(U3-RESV-Pad19)") (class "Default")
      (node (ref "U3") (pin "19") (pinfunction "RESV_19") (pintype "passive+no_connect"))
    )
    (net (code "71") (name "unconnected-(U3-RESV-Pad21)") (class "Default")
      (node (ref "U3") (pin "21") (pinfunction "RESV_21") (pintype "passive+no_connect"))
    )
    (net (code "72") (name "unconnected-(U4-OSCI-Pad27)") (class "Default")
      (node (ref "U4") (pin "27") (pinfunction "OSCI_27") (pintype "passive"))
    )
    (net (code "73") (name "unconnected-(U4-OSCO-Pad28)") (class "Default")
      (node (ref "U4") (pin "28") (pinfunction "OSCO_28") (pintype "passive"))
    )
    (net (code "74") (name "unconnected-(U4-TXDEN-Pad13)") (class "Default")
      (node (ref "U4") (pin "13") (pinfunction "TXDEN_13") (pintype "passive"))
    )
    (net (code "75") (name "unconnected-(U4-~{CTS}-Pad11)") (class "Default")
      (node (ref "U4") (pin "11") (pinfunction "~{CTS}_11") (pintype "passive"))
    )
    (net (code "76") (name "unconnected-(U4-~{DCD}-Pad10)") (class "Default")
      (node (ref "U4") (pin "10") (pinfunction "~{DCD}_10") (pintype "passive"))
    )
    (net (code "77") (name "unconnected-(U4-~{DIR}-Pad2)") (class "Default")
      (node (ref "U4") (pin "2") (pinfunction "~{DIR}_2") (pintype "passive"))
    )
    (net (code "78") (name "unconnected-(U4-~{DSR}-Pad9)") (class "Default")
      (node (ref "U4") (pin "9") (pinfunction "~{DSR}_9") (pintype "passive"))
    )
    (net (code "79") (name "unconnected-(U4-~{PWREN}-Pad14)") (class "Default")
      (node (ref "U4") (pin "14") (pinfunction "~{PWREN}_14") (pintype "passive"))
    )
    (net (code "80") (name "unconnected-(U4-~{RI}-Pad6)") (class "Default")
      (node (ref "U4") (pin "6") (pinfunction "~{RI}_6") (pintype "passive"))
    )
    (net (code "81") (name "unconnected-(U4-~{RTS}-Pad3)") (class "Default")
      (node (ref "U4") (pin "3") (pinfunction "~{RTS}_3") (pintype "passive"))
    )
    (net (code "82") (name "unconnected-(U4-~{RXLED}-Pad22)") (class "Default")
      (node (ref "U4") (pin "22") (pinfunction "~{RXLED}_22") (pintype "passive"))
    )
    (net (code "83") (name "unconnected-(U4-~{SLEEP}-Pad12)") (class "Default")
      (node (ref "U4") (pin "12") (pinfunction "~{SLEEP}_12") (pintype "passive"))
    )
    (net (code "84") (name "unconnected-(U4-~{TXLED}-Pad23)") (class "Default")
      (node (ref "U4") (pin "23") (pinfunction "~{TXLED}_23") (pintype "passive"))
    )
    (net (code "85") (name "unconnected-(U7-ADC6-Pad19)") (class "Default")
      (node (ref "U7") (pin "19") (pinfunction "ADC6_19") (pintype "input+no_connect"))
    )
    (net (code "86") (name "unconnected-(U7-ADC7-Pad22)") (class "Default")
      (node (ref "U7") (pin "22") (pinfunction "ADC7_22") (pintype "input+no_connect"))
    )
    (net (code "87") (name "unconnected-(U7-PC0_(ADC0)-Pad23)") (class "Default")
      (node (ref "U7") (pin "23") (pinfunction "PC0_(ADC0)_23") (pintype "bidirectional+no_connect"))
    )
    (net (code "88") (name "unconnected-(U7-PC1_(ADC1)-Pad24)") (class "Default")
      (node (ref "U7") (pin "24") (pinfunction "PC1_(ADC1)_24") (pintype "bidirectional+no_connect"))
    )
    (net (code "89") (name "unconnected-(U7-PC2_(ADC2)-Pad25)") (class "Default")
      (node (ref "U7") (pin "25") (pinfunction "PC2_(ADC2)_25") (pintype "bidirectional+no_connect"))
    )
    (net (code "90") (name "unconnected-(U7-PC3_(ADC3)-Pad26)") (class "Default")
      (node (ref "U7") (pin "26") (pinfunction "PC3_(ADC3)_26") (pintype "bidirectional+no_connect"))
    )
  )
)
